# Power.net
KiCad netlist of a schematic drawn in Altium Designer
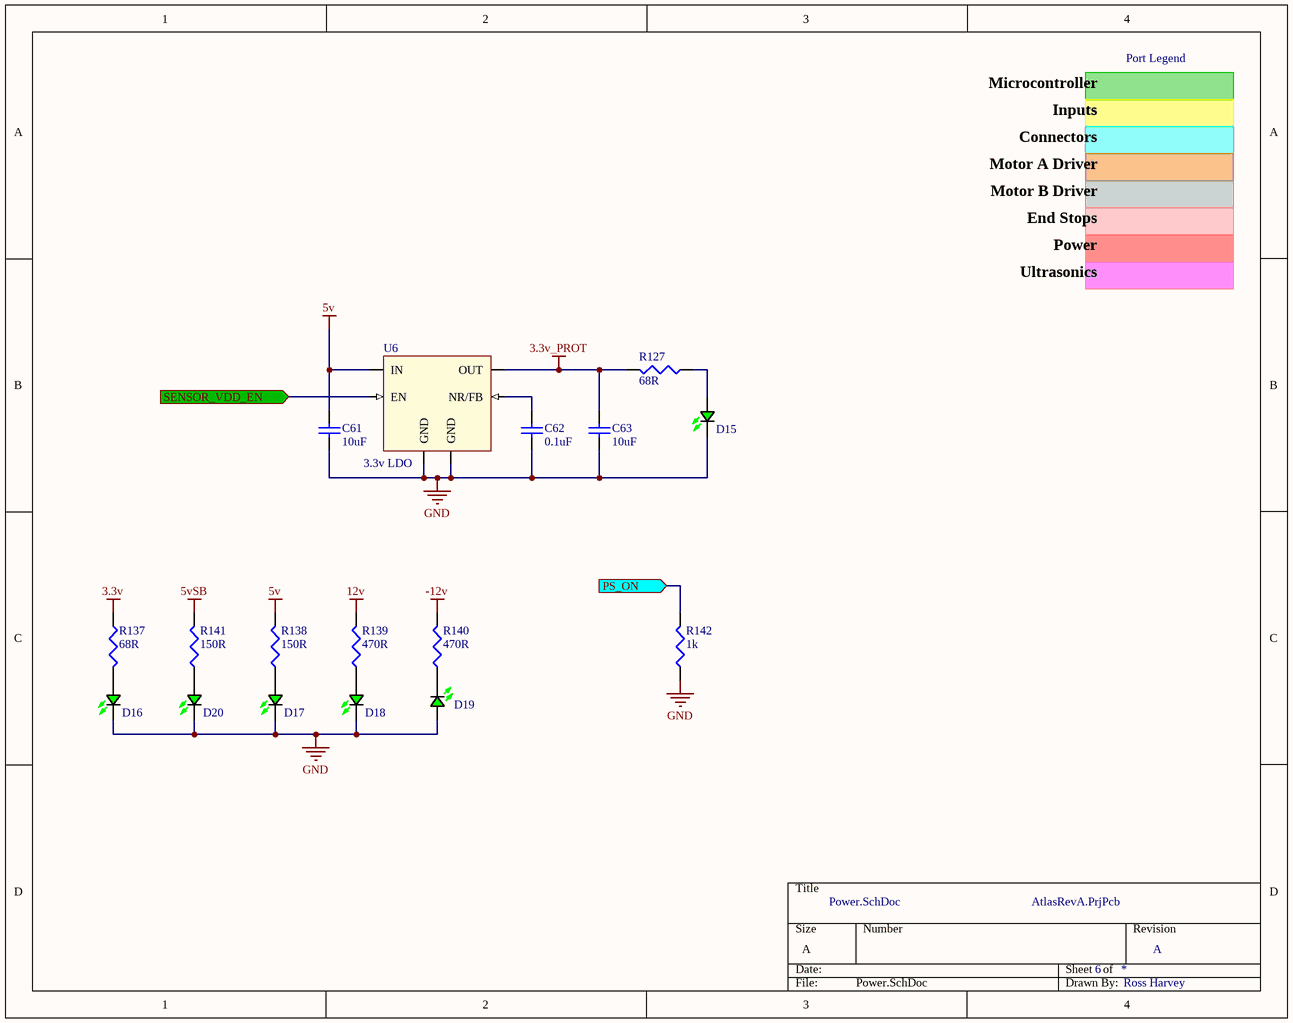
[diagram p0: Power.SchDoc]

(export (version "E")
  (design (tool "Eeschema 10.0.6"))
  (components
    (comp (ref "C61") (value "10uF") (footprint "CAP1206R") (libsource (lib "Altium Library") (part "10uF")))
    (comp (ref "C62")
      (value "0.1uF")
      (footprint "CAP0603W")
      (libsource (lib "Altium Library") (part "0.1uF"))
    )
    (comp (ref "C63") (value "10uF") (footprint "CAP1206R") (libsource (lib "Altium Library") (part "10uF")))
    (comp (ref "D15")
      (value "LTST-S270KGKT")
      (footprint "LED Green 0603")
      (fields (field (name "MFG") "Lite On"))
      (libsource (lib "Altium Library") (part "LED Green 0603"))
    )
    (comp (ref "D16")
      (value "LTST-S270KGKT")
      (footprint "LED Green 0603")
      (fields (field (name "MFG") "Lite On"))
      (libsource (lib "Altium Library") (part "LED Green 0603"))
    )
    (comp (ref "D17")
      (value "LTST-S270KGKT")
      (footprint "LED Green 0603")
      (fields (field (name "MFG") "Lite On"))
      (libsource (lib "Altium Library") (part "LED Green 0603"))
    )
    (comp (ref "D18")
      (value "LTST-S270KGKT")
      (footprint "LED Green 0603")
      (fields (field (name "MFG") "Lite On"))
      (libsource (lib "Altium Library") (part "LED Green 0603"))
    )
    (comp (ref "D19")
      (value "LTST-S270KGKT")
      (footprint "LED Green 0603")
      (fields (field (name "MFG") "Lite On"))
      (libsource (lib "Altium Library") (part "LED Green 0603"))
    )
    (comp (ref "D20")
      (value "LTST-S270KGKT")
      (footprint "LED Green 0603")
      (fields (field (name "MFG") "Lite On"))
      (libsource (lib "Altium Library") (part "LED Green 0603"))
    )
    (comp (ref "R127")
      (value "68R")
      (footprint "RES0603W")
      (fields (field (name "TOLERANCE") "1%") (field (name "POWER") "0.1W") (field (name "MFG") "Vishay"))
      (libsource (lib "Altium Library") (part "68R (0603)"))
    )
    (comp (ref "R137")
      (value "68R")
      (footprint "RES0603W")
      (fields (field (name "TOLERANCE") "1%") (field (name "POWER") "0.1W") (field (name "MFG") "Vishay"))
      (libsource (lib "Altium Library") (part "68R (0603)"))
    )
    (comp (ref "R138")
      (value "150R")
      (footprint "RES0603W")
      (fields (field (name "TOLERANCE") "1%") (field (name "POWER") "0.1W") (field (name "MFG") "Vishay"))
      (libsource (lib "Altium Library") (part "150R (0603)"))
    )
    (comp (ref "R139")
      (value "470R")
      (footprint "RES0603W")
      (fields (field (name "TOLERANCE") "1%") (field (name "POWER") "0.1W") (field (name "MFG") "Vishay"))
      (libsource (lib "Altium Library") (part "470R (0603)"))
    )
    (comp (ref "R140")
      (value "470R")
      (footprint "RES0603W")
      (fields (field (name "TOLERANCE") "1%") (field (name "POWER") "0.1W") (field (name "MFG") "Vishay"))
      (libsource (lib "Altium Library") (part "470R (0603)"))
    )
    (comp (ref "R141")
      (value "150R")
      (footprint "RES0603W")
      (fields (field (name "TOLERANCE") "1%") (field (name "POWER") "0.1W") (field (name "MFG") "Vishay"))
      (libsource (lib "Altium Library") (part "150R (0603)"))
    )
    (comp (ref "R142")
      (value "1k")
      (footprint "RES0603W")
      (fields (field (name "TOLERANCE") "1%") (field (name "POWER") "0.1W") (field (name "MFG") "Vishay"))
      (libsource (lib "Altium Library") (part "1k (0603)"))
    )
    (comp (ref "U6")
      (value "3.3v LDO")
      (footprint "SOT-223-6")
      (fields (field (name "MFG") "TI"))
      (libsource (lib "Altium Library") (part "TPS73633DCQR"))
    )
  )
  (nets
    (net (code "1") (name "-12v") (class "Default")
      (node (ref "R140") (pin "2") (pinfunction "2_2") (pintype "passive"))
    )
    (net (code "2") (name "/PS_ON") (class "Default")
      (node (ref "R142") (pin "2") (pinfunction "2_2") (pintype "passive"))
    )
    (net (code "3") (name "/SENSOR_VDD_EN") (class "Default")
      (node (ref "U6") (pin "5") (pinfunction "EN_5") (pintype "input"))
    )
    (net (code "4") (name "3.3v") (class "Default")
      (node (ref "R137") (pin "1") (pinfunction "1_1") (pintype "passive"))
    )
    (net (code "5") (name "3.3v_PROT") (class "Default")
      (node (ref "C63") (pin "2") (pinfunction "2_2") (pintype "passive"))
      (node (ref "R127") (pin "2") (pinfunction "2_2") (pintype "passive"))
      (node (ref "U6") (pin "2") (pinfunction "OUT_2") (pintype "power_in"))
    )
    (net (code "6") (name "5v") (class "Default")
      (node (ref "C61") (pin "2") (pinfunction "2_2") (pintype "passive"))
      (node (ref "R138") (pin "2") (pinfunction "2_2") (pintype "passive"))
      (node (ref "U6") (pin "1") (pinfunction "IN_1") (pintype "power_in"))
    )
    (net (code "7") (name "5vSB") (class "Default")
      (node (ref "R141") (pin "2") (pinfunction "2_2") (pintype "passive"))
    )
    (net (code "8") (name "12v") (class "Default")
      (node (ref "R139") (pin "2") (pinfunction "2_2") (pintype "passive"))
    )
    (net (code "9") (name "GND") (class "Default")
      (node (ref "C61") (pin "1") (pinfunction "1_1") (pintype "passive"))
      (node (ref "C62") (pin "2") (pinfunction "2_2") (pintype "passive"))
      (node (ref "C63") (pin "1") (pinfunction "1_1") (pintype "passive"))
      (node (ref "D15") (pin "1") (pinfunction "K_1") (pintype "passive"))
      (node (ref "D16") (pin "1") (pinfunction "K_1") (pintype "passive"))
      (node (ref "D17") (pin "1") (pinfunction "K_1") (pintype "passive"))
      (node (ref "D18") (pin "1") (pinfunction "K_1") (pintype "passive"))
      (node (ref "D19") (pin "2") (pinfunction "A_2") (pintype "passive"))
      (node (ref "D20") (pin "1") (pinfunction "K_1") (pintype "passive"))
      (node (ref "R142") (pin "1") (pinfunction "1_1") (pintype "passive"))
      (node (ref "U6") (pin "3") (pinfunction "GND_3") (pintype "power_in"))
      (node (ref "U6") (pin "6") (pinfunction "GND_6") (pintype "power_in"))
    )
    (net (code "10") (name "Net-(D15-A)") (class "Default")
      (node (ref "D15") (pin "2") (pinfunction "A_2") (pintype "passive"))
      (node (ref "R127") (pin "1") (pinfunction "1_1") (pintype "passive"))
    )
    (net (code "11") (name "Net-(D16-A)") (class "Default")
      (node (ref "D16") (pin "2") (pinfunction "A_2") (pintype "passive"))
      (node (ref "R137") (pin "2") (pinfunction "2_2") (pintype "passive"))
    )
    (net (code "12") (name "Net-(D17-A)") (class "Default")
      (node (ref "D17") (pin "2") (pinfunction "A_2") (pintype "passive"))
      (node (ref "R138") (pin "1") (pinfunction "1_1") (pintype "passive"))
    )
    (net (code "13") (name "Net-(D18-A)") (class "Default")
      (node (ref "D18") (pin "2") (pinfunction "A_2") (pintype "passive"))
      (node (ref "R139") (pin "1") (pinfunction "1_1") (pintype "passive"))
    )
    (net (code "14") (name "Net-(D19-K)") (class "Default")
      (node (ref "D19") (pin "1") (pinfunction "K_1") (pintype "passive"))
      (node (ref "R140") (pin "1") (pinfunction "1_1") (pintype "passive"))
    )
    (net (code "15") (name "Net-(D20-A)") (class "Default")
      (node (ref "D20") (pin "2") (pinfunction "A_2") (pintype "passive"))
      (node (ref "R141") (pin "1") (pinfunction "1_1") (pintype "passive"))
    )
    (net (code "16") (name "Net-(U6-NR{slash}FB)") (class "Default")
      (node (ref "C62") (pin "1") (pinfunction "1_1") (pintype "passive"))
      (node (ref "U6") (pin "4") (pinfunction "NR/FB_4") (pintype "input"))
    )
  )
)
